# LPC1115_4TE_TOP_V1_1.net
KiCad netlist of a schematic drawn in EAGLE
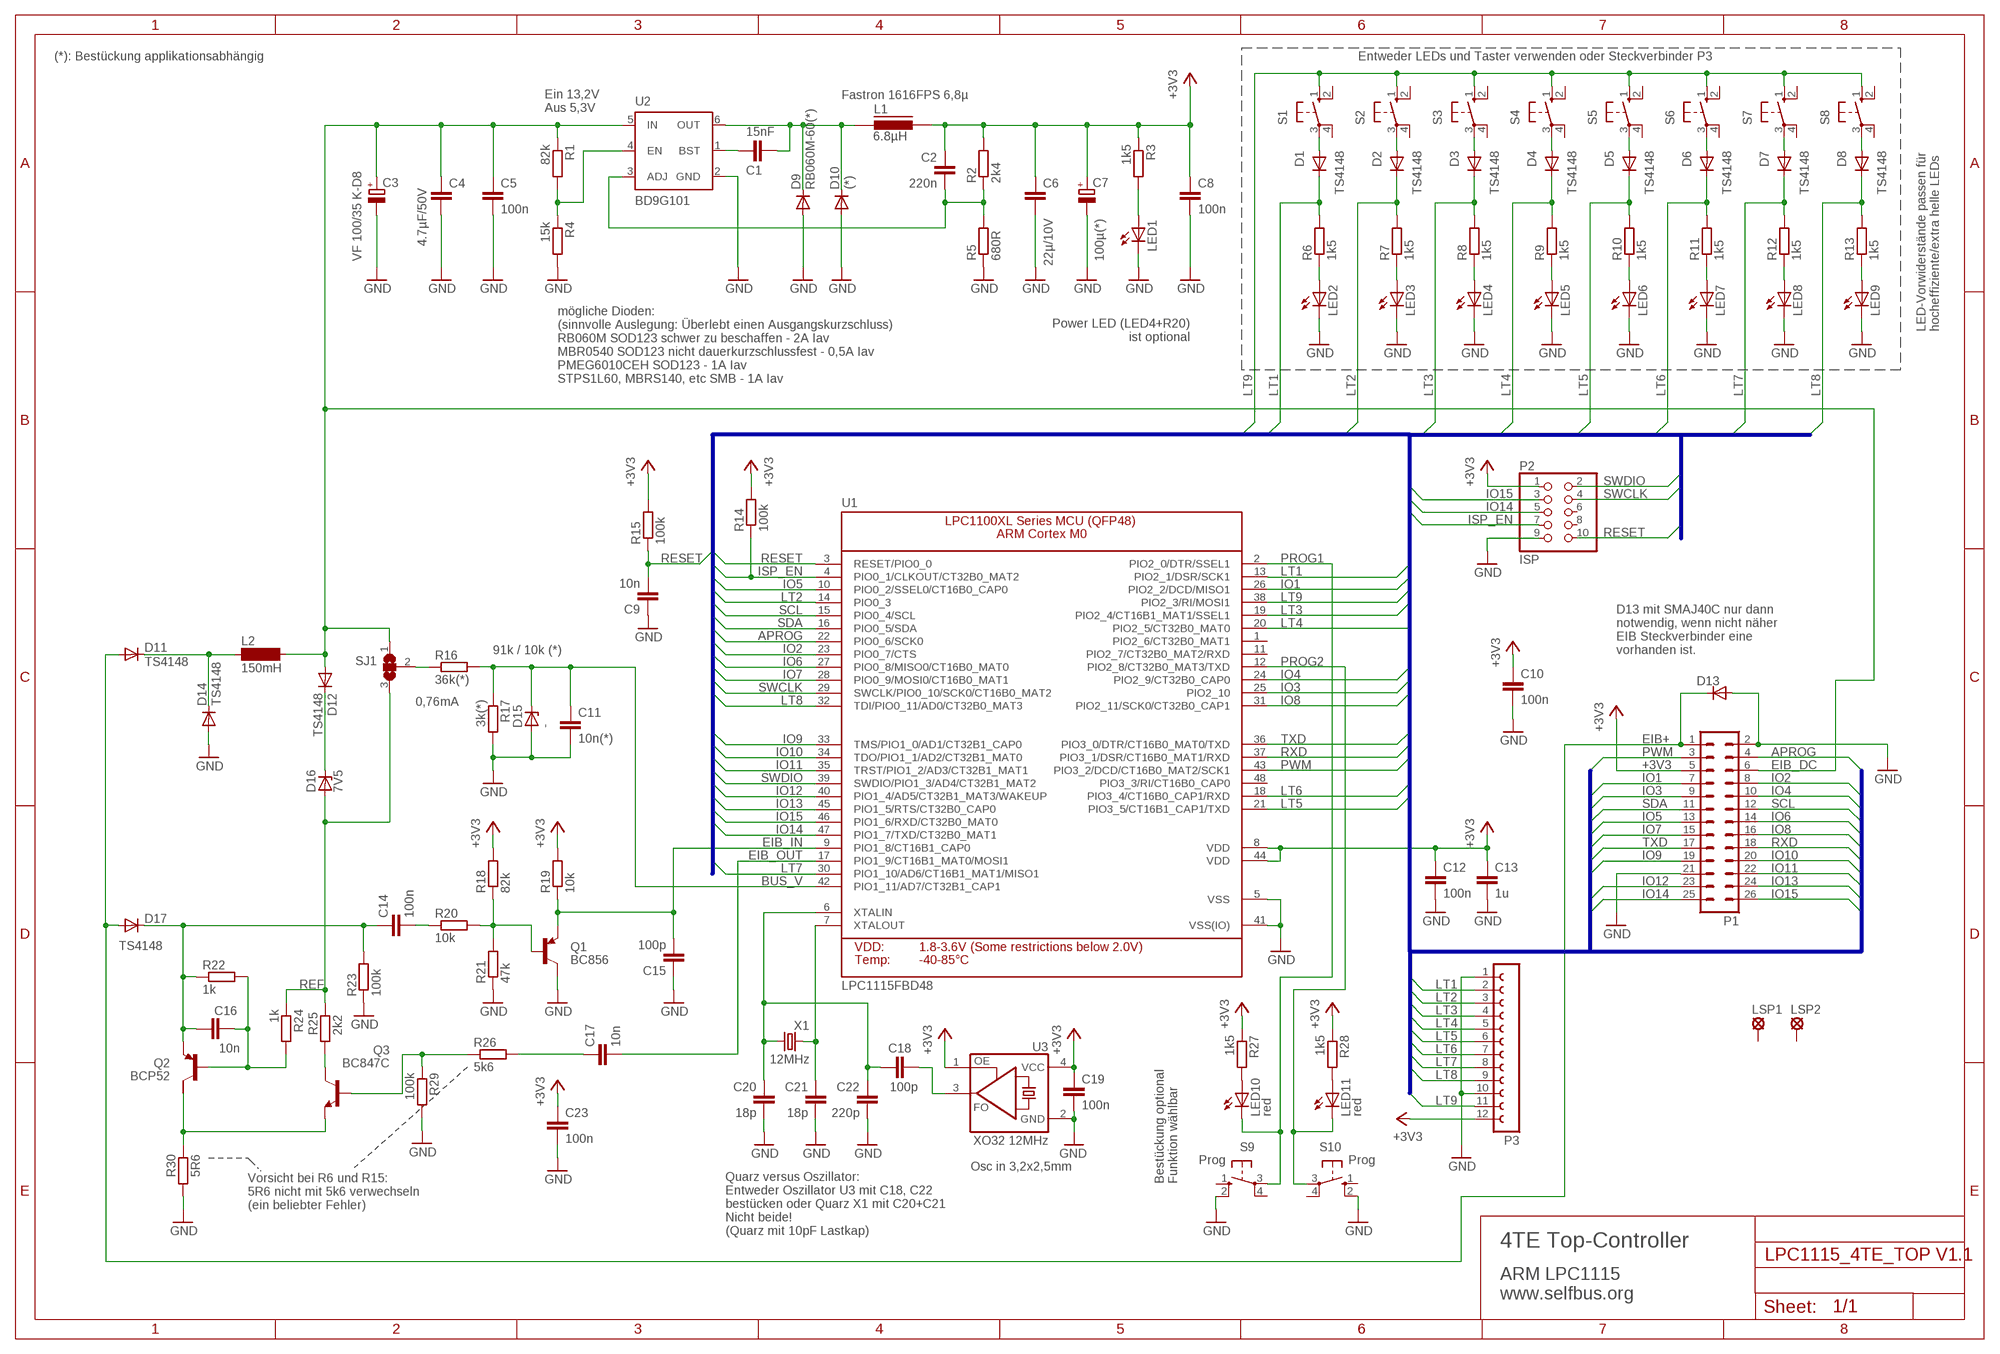
[diagram p0: schematic, sheet 1]

(export (version "E")
  (design (tool "Eeschema 10.0.6"))
  (components
    (comp (ref "C1")
      (value "15nF")
      (footprint "eagle-import:R0805M")
      (libsource (lib "eagle-import") (part "C-EUC0805M"))
    )
    (comp (ref "C2")
      (value "220n")
      (footprint "eagle-import:R0805M")
      (libsource (lib "eagle-import") (part "C-EUC0805M"))
    )
    (comp (ref "C3")
      (value "VF 100/35 K-D8")
      (footprint "eagle-import:ESMD-D")
      (libsource (lib "eagle-import") (part "CPOL-EUESMD-D"))
    )
    (comp (ref "C4")
      (value "4.7µF/50V")
      (footprint "eagle-import:R1206M")
      (libsource (lib "eagle-import") (part "C-EUC1206M"))
    )
    (comp (ref "C5")
      (value "100n")
      (footprint "eagle-import:R0805M")
      (libsource (lib "eagle-import") (part "C-EUC0805M"))
    )
    (comp (ref "C6")
      (value "22µ/10V")
      (footprint "eagle-import:C1210K")
      (libsource (lib "eagle-import") (part "C-EUC1210K"))
    )
    (comp (ref "C7")
      (value "100µ(*)")
      (footprint "eagle-import:ESMD-D")
      (libsource (lib "eagle-import") (part "CPOL-EUESMD-D"))
    )
    (comp (ref "C8")
      (value "100n")
      (footprint "eagle-import:R0805M")
      (libsource (lib "eagle-import") (part "C-EUC0805M"))
    )
    (comp (ref "C9")
      (value "10n")
      (footprint "eagle-import:R0805M")
      (libsource (lib "eagle-import") (part "C-EUC0805M"))
    )
    (comp (ref "C10")
      (value "100n")
      (footprint "eagle-import:R0805M")
      (libsource (lib "eagle-import") (part "C-EUC0805M"))
    )
    (comp (ref "C11")
      (value "10n(*)")
      (footprint "eagle-import:R0805M")
      (libsource (lib "eagle-import") (part "C-EUC0805M"))
    )
    (comp (ref "C12")
      (value "100n")
      (footprint "eagle-import:R0805M")
      (libsource (lib "eagle-import") (part "C-EUC0805M"))
    )
    (comp (ref "C13")
      (value "1u")
      (footprint "eagle-import:R0805M")
      (libsource (lib "eagle-import") (part "C-EUC0805M"))
    )
    (comp (ref "C14")
      (value "100n")
      (footprint "eagle-import:R0805M")
      (libsource (lib "eagle-import") (part "C-EUC0805M"))
    )
    (comp (ref "C15")
      (value "100p")
      (footprint "eagle-import:R0805M")
      (libsource (lib "eagle-import") (part "C-EUC0805M"))
    )
    (comp (ref "C16")
      (value "10n")
      (footprint "eagle-import:R0805M")
      (libsource (lib "eagle-import") (part "C-EUC0805M"))
    )
    (comp (ref "C17")
      (value "10n")
      (footprint "eagle-import:R0805M")
      (libsource (lib "eagle-import") (part "C-EUC0805M"))
    )
    (comp (ref "C18")
      (value "100p")
      (footprint "eagle-import:R0805M")
      (libsource (lib "eagle-import") (part "C-EUC0805M"))
    )
    (comp (ref "C19")
      (value "100n")
      (footprint "eagle-import:R0805M")
      (libsource (lib "eagle-import") (part "C-EUC0805M"))
    )
    (comp (ref "C20")
      (value "18p")
      (footprint "eagle-import:R0805M")
      (libsource (lib "eagle-import") (part "C-EUC0805M"))
    )
    (comp (ref "C21")
      (value "18p")
      (footprint "eagle-import:R0805M")
      (libsource (lib "eagle-import") (part "C-EUC0805M"))
    )
    (comp (ref "C22")
      (value "220p")
      (footprint "eagle-import:R0805M")
      (libsource (lib "eagle-import") (part "C-EUC0805M"))
    )
    (comp (ref "C23")
      (value "100n")
      (footprint "eagle-import:R0805M")
      (libsource (lib "eagle-import") (part "C-EUC0805M"))
    )
    (comp (ref "D1")
      (value "TS4148")
      (footprint "eagle-import:D0805")
      (libsource (lib "eagle-import") (part "DIODE-D0805"))
    )
    (comp (ref "D2")
      (value "TS4148")
      (footprint "eagle-import:D0805")
      (libsource (lib "eagle-import") (part "DIODE-D0805"))
    )
    (comp (ref "D3")
      (value "TS4148")
      (footprint "eagle-import:D0805")
      (libsource (lib "eagle-import") (part "DIODE-D0805"))
    )
    (comp (ref "D4")
      (value "TS4148")
      (footprint "eagle-import:D0805")
      (libsource (lib "eagle-import") (part "DIODE-D0805"))
    )
    (comp (ref "D5")
      (value "TS4148")
      (footprint "eagle-import:D0805")
      (libsource (lib "eagle-import") (part "DIODE-D0805"))
    )
    (comp (ref "D6")
      (value "TS4148")
      (footprint "eagle-import:D0805")
      (libsource (lib "eagle-import") (part "DIODE-D0805"))
    )
    (comp (ref "D7")
      (value "TS4148")
      (footprint "eagle-import:D0805")
      (libsource (lib "eagle-import") (part "DIODE-D0805"))
    )
    (comp (ref "D8")
      (value "TS4148")
      (footprint "eagle-import:D0805")
      (libsource (lib "eagle-import") (part "DIODE-D0805"))
    )
    (comp (ref "D9")
      (value "RB060M-60(*)")
      (footprint "eagle-import:SOD123")
      (libsource (lib "eagle-import") (part "DIODE-SOD123"))
    )
    (comp (ref "D10")
      (value "(*)")
      (footprint "eagle-import:SMB")
      (libsource (lib "eagle-import") (part "DIODE-SMB"))
    )
    (comp (ref "D11")
      (value "TS4148")
      (footprint "eagle-import:D0805")
      (libsource (lib "eagle-import") (part "DIODE-D0805"))
    )
    (comp (ref "D12")
      (value "TS4148")
      (footprint "eagle-import:D0805")
      (libsource (lib "eagle-import") (part "DIODE-D0805"))
    )
    (comp (ref "D13")
      (value "D-SMB")
      (footprint "eagle-import:SMB")
      (libsource (lib "eagle-import") (part "D-SMB"))
    )
    (comp (ref "D14")
      (value "TS4148")
      (footprint "eagle-import:D0805")
      (libsource (lib "eagle-import") (part "DIODE-D0805"))
    )
    (comp (ref "D15")
      (value "-")
      (footprint "eagle-import:SOT23")
      (libsource (lib "eagle-import") (part "ZENER-DIODESOT23"))
    )
    (comp (ref "D16")
      (value "7V5")
      (footprint "eagle-import:SOT23")
      (libsource (lib "eagle-import") (part "ZENER-DIODESOT23"))
    )
    (comp (ref "D17")
      (value "TS4148")
      (footprint "eagle-import:D0805")
      (libsource (lib "eagle-import") (part "DIODE-D0805"))
    )
    (comp (ref "L1")
      (value "6.8µH")
      (footprint "eagle-import:1616FPS")
      (libsource (lib "eagle-import") (part "IND_FASTRON_1616FPSB"))
    )
    (comp (ref "L2")
      (value "150mH")
      (footprint "eagle-import:BS11_LIEGEND")
      (libsource (lib "eagle-import") (part "SD12BS11_LIEGEND"))
    )
    (comp (ref "LED1")
      (value "LEDSMT1206")
      (footprint "eagle-import:1206")
      (libsource (lib "eagle-import") (part "LEDSMT1206"))
    )
    (comp (ref "LED2")
      (value "LEDSMT1206")
      (footprint "eagle-import:1206")
      (libsource (lib "eagle-import") (part "LEDSMT1206"))
    )
    (comp (ref "LED3")
      (value "LEDSMT1206")
      (footprint "eagle-import:1206")
      (libsource (lib "eagle-import") (part "LEDSMT1206"))
    )
    (comp (ref "LED4")
      (value "LEDSMT1206")
      (footprint "eagle-import:1206")
      (libsource (lib "eagle-import") (part "LEDSMT1206"))
    )
    (comp (ref "LED5")
      (value "LEDSMT1206")
      (footprint "eagle-import:1206")
      (libsource (lib "eagle-import") (part "LEDSMT1206"))
    )
    (comp (ref "LED6")
      (value "LEDSMT1206")
      (footprint "eagle-import:1206")
      (libsource (lib "eagle-import") (part "LEDSMT1206"))
    )
    (comp (ref "LED7")
      (value "LEDSMT1206")
      (footprint "eagle-import:1206")
      (libsource (lib "eagle-import") (part "LEDSMT1206"))
    )
    (comp (ref "LED8")
      (value "LEDSMT1206")
      (footprint "eagle-import:1206")
      (libsource (lib "eagle-import") (part "LEDSMT1206"))
    )
    (comp (ref "LED9")
      (value "LEDSMT1206")
      (footprint "eagle-import:1206")
      (libsource (lib "eagle-import") (part "LEDSMT1206"))
    )
    (comp (ref "LED10")
      (value "red")
      (footprint "eagle-import:1206")
      (libsource (lib "eagle-import") (part "LEDSMT1206"))
    )
    (comp (ref "LED11")
      (value "red")
      (footprint "eagle-import:1206")
      (libsource (lib "eagle-import") (part "LEDSMT1206"))
    )
    (comp (ref "LSP1")
      (value "SE13_SM")
      (footprint "eagle-import:SE13_SM")
      (libsource (lib "eagle-import") (part "SE13_SM"))
    )
    (comp (ref "LSP2")
      (value "SE13_SM")
      (footprint "eagle-import:SE13_SM")
      (libsource (lib "eagle-import") (part "SE13_SM"))
    )
    (comp (ref "P1")
      (value "ML26")
      (footprint "eagle-import:ML26")
      (libsource (lib "eagle-import") (part "ML26"))
    )
    (comp (ref "P2")
      (value "ISP")
      (footprint "eagle-import:2X05M")
      (libsource (lib "eagle-import") (part "PINHD-2X05_2.00"))
    )
    (comp (ref "P3")
      (value "FE12-1")
      (footprint "eagle-import:FE12")
      (libsource (lib "eagle-import") (part "FE12-1"))
    )
    (comp (ref "Q1")
      (value "BC856")
      (footprint "eagle-import:SOT23-BEC")
      (libsource (lib "eagle-import") (part "BC856SMDB"))
    )
    (comp (ref "Q2")
      (value "BCP52")
      (footprint "eagle-import:SOT223")
      (libsource (lib "eagle-import") (part "FZT753SMD"))
    )
    (comp (ref "Q3")
      (value "BC847C")
      (footprint "eagle-import:SOT23")
      (libsource (lib "eagle-import") (part "BC847"))
    )
    (comp (ref "R1")
      (value "82k")
      (footprint "eagle-import:R0805M")
      (libsource (lib "eagle-import") (part "R-EU_R0805M"))
    )
    (comp (ref "R2")
      (value "2k4")
      (footprint "eagle-import:R0805M")
      (libsource (lib "eagle-import") (part "R-EU_R0805M"))
    )
    (comp (ref "R3")
      (value "1k5")
      (footprint "eagle-import:R0805M")
      (libsource (lib "eagle-import") (part "R-EU_R0805M"))
    )
    (comp (ref "R4")
      (value "15k")
      (footprint "eagle-import:R0805M")
      (libsource (lib "eagle-import") (part "R-EU_R0805M"))
    )
    (comp (ref "R5")
      (value "680R")
      (footprint "eagle-import:R0805M")
      (libsource (lib "eagle-import") (part "R-EU_R0805M"))
    )
    (comp (ref "R6")
      (value "1k5")
      (footprint "eagle-import:R0805M")
      (libsource (lib "eagle-import") (part "R-EU_R0805M"))
    )
    (comp (ref "R7")
      (value "1k5")
      (footprint "eagle-import:R0805M")
      (libsource (lib "eagle-import") (part "R-EU_R0805M"))
    )
    (comp (ref "R8")
      (value "1k5")
      (footprint "eagle-import:R0805M")
      (libsource (lib "eagle-import") (part "R-EU_R0805M"))
    )
    (comp (ref "R9")
      (value "1k5")
      (footprint "eagle-import:R0805M")
      (libsource (lib "eagle-import") (part "R-EU_R0805M"))
    )
    (comp (ref "R10")
      (value "1k5")
      (footprint "eagle-import:R0805M")
      (libsource (lib "eagle-import") (part "R-EU_R0805M"))
    )
    (comp (ref "R11")
      (value "1k5")
      (footprint "eagle-import:R0805M")
      (libsource (lib "eagle-import") (part "R-EU_R0805M"))
    )
    (comp (ref "R12")
      (value "1k5")
      (footprint "eagle-import:R0805M")
      (libsource (lib "eagle-import") (part "R-EU_R0805M"))
    )
    (comp (ref "R13")
      (value "1k5")
      (footprint "eagle-import:R0805M")
      (libsource (lib "eagle-import") (part "R-EU_R0805M"))
    )
    (comp (ref "R14")
      (value "100k")
      (footprint "eagle-import:R0805M")
      (libsource (lib "eagle-import") (part "R-EU_R0805M"))
    )
    (comp (ref "R15")
      (value "100k")
      (footprint "eagle-import:R0805M")
      (libsource (lib "eagle-import") (part "R-EU_R0805M"))
    )
    (comp (ref "R16")
      (value "36k(*)")
      (footprint "eagle-import:R0805M")
      (libsource (lib "eagle-import") (part "R-EU_R0805M"))
    )
    (comp (ref "R17")
      (value "3k(*)")
      (footprint "eagle-import:R0805M")
      (libsource (lib "eagle-import") (part "R-EU_R0805M"))
    )
    (comp (ref "R18")
      (value "82k")
      (footprint "eagle-import:R0805M")
      (libsource (lib "eagle-import") (part "R-EU_R0805M"))
    )
    (comp (ref "R19")
      (value "10k")
      (footprint "eagle-import:R0805M")
      (libsource (lib "eagle-import") (part "R-EU_R0805M"))
    )
    (comp (ref "R20")
      (value "10k")
      (footprint "eagle-import:R0805M")
      (libsource (lib "eagle-import") (part "R-EU_R0805M"))
    )
    (comp (ref "R21")
      (value "47k")
      (footprint "eagle-import:R0805M")
      (libsource (lib "eagle-import") (part "R-EU_R0805M"))
    )
    (comp (ref "R22")
      (value "1k")
      (footprint "eagle-import:R0805M")
      (libsource (lib "eagle-import") (part "R-EU_R0805M"))
    )
    (comp (ref "R23")
      (value "100k")
      (footprint "eagle-import:R0805M")
      (libsource (lib "eagle-import") (part "R-EU_R0805M"))
    )
    (comp (ref "R24")
      (value "1k")
      (footprint "eagle-import:R0805M")
      (libsource (lib "eagle-import") (part "R-EU_R0805M"))
    )
    (comp (ref "R25")
      (value "2k2")
      (footprint "eagle-import:R0805M")
      (libsource (lib "eagle-import") (part "R-EU_R0805M"))
    )
    (comp (ref "R26")
      (value "5k6")
      (footprint "eagle-import:R0805M")
      (libsource (lib "eagle-import") (part "R-EU_R0805M"))
    )
    (comp (ref "R27")
      (value "1k5")
      (footprint "eagle-import:R0805M")
      (libsource (lib "eagle-import") (part "R-EU_R0805M"))
    )
    (comp (ref "R28")
      (value "1k5")
      (footprint "eagle-import:R0805M")
      (libsource (lib "eagle-import") (part "R-EU_R0805M"))
    )
    (comp (ref "R29")
      (value "100k")
      (footprint "eagle-import:R0805M")
      (libsource (lib "eagle-import") (part "R-EU_R0805M"))
    )
    (comp (ref "R30")
      (value "5R6")
      (footprint "eagle-import:R1206M")
      (libsource (lib "eagle-import") (part "R-EU_R1206M"))
    )
    (comp (ref "S1")
      (value "10-XXSMD")
      (footprint "eagle-import:B3F-10XX_SMD")
      (libsource (lib "eagle-import") (part "10-XXSMD"))
    )
    (comp (ref "S2")
      (value "10-XXSMD")
      (footprint "eagle-import:B3F-10XX_SMD")
      (libsource (lib "eagle-import") (part "10-XXSMD"))
    )
    (comp (ref "S3")
      (value "10-XXSMD")
      (footprint "eagle-import:B3F-10XX_SMD")
      (libsource (lib "eagle-import") (part "10-XXSMD"))
    )
    (comp (ref "S4")
      (value "10-XXSMD")
      (footprint "eagle-import:B3F-10XX_SMD")
      (libsource (lib "eagle-import") (part "10-XXSMD"))
    )
    (comp (ref "S5")
      (value "10-XXSMD")
      (footprint "eagle-import:B3F-10XX_SMD")
      (libsource (lib "eagle-import") (part "10-XXSMD"))
    )
    (comp (ref "S6")
      (value "10-XXSMD")
      (footprint "eagle-import:B3F-10XX_SMD")
      (libsource (lib "eagle-import") (part "10-XXSMD"))
    )
    (comp (ref "S7")
      (value "10-XXSMD")
      (footprint "eagle-import:B3F-10XX_SMD")
      (libsource (lib "eagle-import") (part "10-XXSMD"))
    )
    (comp (ref "S8")
      (value "10-XXSMD")
      (footprint "eagle-import:B3F-10XX_SMD")
      (libsource (lib "eagle-import") (part "10-XXSMD"))
    )
    (comp (ref "S9")
      (value "Prog")
      (footprint "eagle-import:B3F-10XX_SMD")
      (libsource (lib "eagle-import") (part "10-XXSMD"))
    )
    (comp (ref "S10")
      (value "Prog")
      (footprint "eagle-import:B3F-10XX_SMD")
      (libsource (lib "eagle-import") (part "10-XXSMD"))
    )
    (comp (ref "SJ1")
      (value "SJ2W")
      (footprint "eagle-import:SJ_2")
      (libsource (lib "eagle-import") (part "SJ2W"))
    )
    (comp (ref "U1")
      (value "LPC1115FBD48")
      (footprint "eagle-import:LQFP48")
      (libsource (lib "eagle-import") (part "LPC1113/4/5_QFP48_XLSERIES"))
    )
    (comp (ref "U2")
      (value "BD9G101")
      (footprint "eagle-import:SOT23-6MOD")
      (libsource (lib "eagle-import") (part "BD9G101GBD9G101G-SOT23-6MOD"))
    )
    (comp (ref "U3")
      (value "XO32 12MHz")
      (footprint "eagle-import:ASF")
      (libsource (lib "eagle-import") (part "ASFL"))
    )
    (comp (ref "X1")
      (value "12MHz")
      (footprint "eagle-import:ASF")
      (libsource (lib "eagle-import") (part "CRYSTALASF"))
    )
  )
  (nets
    (net (code "1") (name "+3V3") (class "Default")
      (node (ref "C10") (pin "1") (pinfunction "1_1") (pintype "passive"))
      (node (ref "C12") (pin "1") (pinfunction "1_1") (pintype "passive"))
      (node (ref "C13") (pin "1") (pinfunction "1_1") (pintype "passive"))
      (node (ref "C19") (pin "1") (pinfunction "1_1") (pintype "passive"))
      (node (ref "C2") (pin "1") (pinfunction "1_1") (pintype "passive"))
      (node (ref "C23") (pin "1") (pinfunction "1_1") (pintype "passive"))
      (node (ref "C6") (pin "1") (pinfunction "1_1") (pintype "passive"))
      (node (ref "C7") (pin "+") (pinfunction "+_+") (pintype "passive"))
      (node (ref "C8") (pin "1") (pinfunction "1_1") (pintype "passive"))
      (node (ref "L1") (pin "P$2") (pinfunction "2_P$2") (pintype "passive"))
      (node (ref "P1") (pin "5") (pinfunction "5_5") (pintype "passive"))
      (node (ref "P2") (pin "1") (pinfunction "1_1") (pintype "passive"))
      (node (ref "P3") (pin "12") (pinfunction "12_12") (pintype "passive"))
      (node (ref "R14") (pin "2") (pinfunction "2_2") (pintype "passive"))
      (node (ref "R15") (pin "2") (pinfunction "2_2") (pintype "passive"))
      (node (ref "R18") (pin "2") (pinfunction "2_2") (pintype "passive"))
      (node (ref "R19") (pin "2") (pinfunction "2_2") (pintype "passive"))
      (node (ref "R2") (pin "2") (pinfunction "2_2") (pintype "passive"))
      (node (ref "R27") (pin "1") (pinfunction "1_1") (pintype "passive"))
      (node (ref "R28") (pin "1") (pinfunction "1_1") (pintype "passive"))
      (node (ref "R3") (pin "1") (pinfunction "1_1") (pintype "passive"))
      (node (ref "U1") (pin "44") (pinfunction "VDD_44") (pintype "power_in"))
      (node (ref "U1") (pin "8") (pinfunction "VDD_8") (pintype "power_in"))
      (node (ref "U3") (pin "1") (pinfunction "OE_1") (pintype "input"))
      (node (ref "U3") (pin "4") (pinfunction "VCC_4") (pintype "power_in"))
    )
    (net (code "2") (name "/APROG") (class "Default")
      (node (ref "P1") (pin "4") (pinfunction "4_4") (pintype "passive"))
      (node (ref "U1") (pin "22") (pinfunction "PIO0_6/SCK0_22") (pintype "bidirectional"))
    )
    (net (code "3") (name "/BUS_V") (class "Default")
      (node (ref "C11") (pin "1") (pinfunction "1_1") (pintype "passive"))
      (node (ref "D15") (pin "3") (pinfunction "C_3") (pintype "passive"))
      (node (ref "R16") (pin "2") (pinfunction "2_2") (pintype "passive"))
      (node (ref "R17") (pin "1") (pinfunction "1_1") (pintype "passive"))
      (node (ref "U1") (pin "42") (pinfunction "PIO1_11/AD7/CT32B1_CAP1_42") (pintype "bidirectional"))
    )
    (net (code "4") (name "/EIB+") (class "Default")
      (node (ref "D11") (pin "A") (pinfunction "A_A") (pintype "passive"))
      (node (ref "D13") (pin "1") (pinfunction "C_1") (pintype "passive"))
      (node (ref "D17") (pin "A") (pinfunction "A_A") (pintype "passive"))
      (node (ref "P1") (pin "1") (pinfunction "1_1") (pintype "passive"))
    )
    (net (code "5") (name "/EIB_DC") (class "Default")
      (node (ref "C3") (pin "+") (pinfunction "+_+") (pintype "passive"))
      (node (ref "C4") (pin "1") (pinfunction "1_1") (pintype "passive"))
      (node (ref "C5") (pin "1") (pinfunction "1_1") (pintype "passive"))
      (node (ref "D12") (pin "A") (pinfunction "A_A") (pintype "passive"))
      (node (ref "L2") (pin "2") (pinfunction "2_2") (pintype "passive"))
      (node (ref "P1") (pin "6") (pinfunction "6_6") (pintype "passive"))
      (node (ref "R1") (pin "1") (pinfunction "1_1") (pintype "passive"))
      (node (ref "SJ1") (pin "1") (pinfunction "1_1") (pintype "passive"))
      (node (ref "U2") (pin "5") (pinfunction "IN_5") (pintype "input"))
    )
    (net (code "6") (name "/EIB_IN") (class "Default")
      (node (ref "C15") (pin "2") (pinfunction "2_2") (pintype "passive"))
      (node (ref "Q1") (pin "E") (pinfunction "E_E") (pintype "passive"))
      (node (ref "R19") (pin "1") (pinfunction "1_1") (pintype "passive"))
      (node (ref "U1") (pin "9") (pinfunction "PIO1_8/CT16B1_CAP0_9") (pintype "bidirectional"))
    )
    (net (code "7") (name "/EIB_OUT") (class "Default")
      (node (ref "C17") (pin "2") (pinfunction "2_2") (pintype "passive"))
      (node (ref "U1") (pin "17") (pinfunction "PIO1_9/CT16B1_MAT0/MOSI1_17") (pintype "bidirectional"))
    )
    (net (code "8") (name "/IO1") (class "Default")
      (node (ref "P1") (pin "7") (pinfunction "7_7") (pintype "passive"))
      (node (ref "U1") (pin "26") (pinfunction "PIO2_2/DCD/MISO1_26") (pintype "bidirectional"))
    )
    (net (code "9") (name "/IO2") (class "Default")
      (node (ref "P1") (pin "8") (pinfunction "8_8") (pintype "passive"))
      (node (ref "U1") (pin "23") (pinfunction "PIO0_7/CTS_23") (pintype "bidirectional"))
    )
    (net (code "10") (name "/IO3") (class "Default")
      (node (ref "P1") (pin "9") (pinfunction "9_9") (pintype "passive"))
      (node (ref "U1") (pin "25") (pinfunction "PIO2_10_25") (pintype "bidirectional"))
    )
    (net (code "11") (name "/IO4") (class "Default")
      (node (ref "P1") (pin "10") (pinfunction "10_10") (pintype "passive"))
      (node (ref "U1") (pin "24") (pinfunction "PIO2_9/CT32B0_CAP0_24") (pintype "bidirectional"))
    )
    (net (code "12") (name "/IO5") (class "Default")
      (node (ref "P1") (pin "13") (pinfunction "13_13") (pintype "passive"))
      (node (ref "U1") (pin "10") (pinfunction "PIO0_2/SSEL0/CT16B0_CAP0_10") (pintype "bidirectional"))
    )
    (net (code "13") (name "/IO6") (class "Default")
      (node (ref "P1") (pin "14") (pinfunction "14_14") (pintype "passive"))
      (node (ref "U1") (pin "27") (pinfunction "PIO0_8/MISO0/CT16B0_MAT0_27") (pintype "bidirectional"))
    )
    (net (code "14") (name "/IO7") (class "Default")
      (node (ref "P1") (pin "15") (pinfunction "15_15") (pintype "passive"))
      (node (ref "U1") (pin "28") (pinfunction "PIO0_9/MOSI0/CT16B0_MAT1_28") (pintype "bidirectional"))
    )
    (net (code "15") (name "/IO8") (class "Default")
      (node (ref "P1") (pin "16") (pinfunction "16_16") (pintype "passive"))
      (node (ref "U1") (pin "31") (pinfunction "PIO2_11/SCK0/CT32B0_CAP1_31") (pintype "bidirectional"))
    )
    (net (code "16") (name "/IO9") (class "Default")
      (node (ref "P1") (pin "19") (pinfunction "19_19") (pintype "passive"))
      (node (ref "U1") (pin "33") (pinfunction "TMS/PIO1_0/AD1/CT32B1_CAP0_33") (pintype "bidirectional"))
    )
    (net (code "17") (name "/IO10") (class "Default")
      (node (ref "P1") (pin "20") (pinfunction "20_20") (pintype "passive"))
      (node (ref "U1") (pin "34") (pinfunction "TDO/PIO1_1/AD2/CT32B1_MAT0_34") (pintype "bidirectional"))
    )
    (net (code "18") (name "/IO11") (class "Default")
      (node (ref "P1") (pin "22") (pinfunction "22_22") (pintype "passive"))
      (node (ref "U1") (pin "35") (pinfunction "TRST/PIO1_2/AD3/CT32B1_MAT1_35") (pintype "bidirectional"))
    )
    (net (code "19") (name "/IO12") (class "Default")
      (node (ref "P1") (pin "23") (pinfunction "23_23") (pintype "passive"))
      (node (ref "U1") (pin "40") (pinfunction "PIO1_4/AD5/CT32B1_MAT3/WAKEUP_40") (pintype "bidirectional"))
    )
    (net (code "20") (name "/IO13") (class "Default")
      (node (ref "P1") (pin "24") (pinfunction "24_24") (pintype "passive"))
      (node (ref "U1") (pin "45") (pinfunction "PIO1_5/RTS/CT32B0_CAP0_45") (pintype "bidirectional"))
    )
    (net (code "21") (name "/IO14") (class "Default")
      (node (ref "P1") (pin "25") (pinfunction "25_25") (pintype "passive"))
      (node (ref "P2") (pin "5") (pinfunction "5_5") (pintype "passive"))
      (node (ref "U1") (pin "47") (pinfunction "PIO1_7/TXD/CT32B0_MAT1_47") (pintype "bidirectional"))
    )
    (net (code "22") (name "/IO15") (class "Default")
      (node (ref "P1") (pin "26") (pinfunction "26_26") (pintype "passive"))
      (node (ref "P2") (pin "3") (pinfunction "3_3") (pintype "passive"))
      (node (ref "U1") (pin "46") (pinfunction "PIO1_6/RXD/CT32B0_MAT0_46") (pintype "bidirectional"))
    )
    (net (code "23") (name "/ISP_EN") (class "Default")
      (node (ref "P2") (pin "7") (pinfunction "7_7") (pintype "passive"))
      (node (ref "R14") (pin "1") (pinfunction "1_1") (pintype "passive"))
      (node (ref "U1") (pin "4") (pinfunction "PIO0_1/CLKOUT/CT32B0_MAT2_4") (pintype "bidirectional"))
    )
    (net (code "24") (name "/LT1") (class "Default")
      (node (ref "D1") (pin "C") (pinfunction "C_C") (pintype "passive"))
      (node (ref "P3") (pin "2") (pinfunction "2_2") (pintype "passive"))
      (node (ref "R6") (pin "2") (pinfunction "2_2") (pintype "passive"))
      (node (ref "U1") (pin "13") (pinfunction "PIO2_1/DSR/SCK1_13") (pintype "bidirectional"))
    )
    (net (code "25") (name "/LT2") (class "Default")
      (node (ref "D2") (pin "C") (pinfunction "C_C") (pintype "passive"))
      (node (ref "P3") (pin "3") (pinfunction "3_3") (pintype "passive"))
      (node (ref "R7") (pin "2") (pinfunction "2_2") (pintype "passive"))
      (node (ref "U1") (pin "14") (pinfunction "PIO0_3_14") (pintype "bidirectional"))
    )
    (net (code "26") (name "/LT3") (class "Default")
      (node (ref "D3") (pin "C") (pinfunction "C_C") (pintype "passive"))
      (node (ref "P3") (pin "4") (pinfunction "4_4") (pintype "passive"))
      (node (ref "R8") (pin "2") (pinfunction "2_2") (pintype "passive"))
      (node (ref "U1") (pin "19") (pinfunction "PIO2_4/CT16B1_MAT1/SSEL1_19") (pintype "bidirectional"))
    )
    (net (code "27") (name "/LT4") (class "Default")
      (node (ref "D4") (pin "C") (pinfunction "C_C") (pintype "passive"))
      (node (ref "P3") (pin "5") (pinfunction "5_5") (pintype "passive"))
      (node (ref "R9") (pin "2") (pinfunction "2_2") (pintype "passive"))
      (node (ref "U1") (pin "20") (pinfunction "PIO2_5/CT32B0_MAT0_20") (pintype "bidirectional"))
    )
    (net (code "28") (name "/LT5") (class "Default")
      (node (ref "D5") (pin "C") (pinfunction "C_C") (pintype "passive"))
      (node (ref "P3") (pin "6") (pinfunction "6_6") (pintype "passive"))
      (node (ref "R10") (pin "2") (pinfunction "2_2") (pintype "passive"))
      (node (ref "U1") (pin "21") (pinfunction "PIO3_5/CT16B1_CAP1/TXD_21") (pintype "bidirectional"))
    )
    (net (code "29") (name "/LT6") (class "Default")
      (node (ref "D6") (pin "C") (pinfunction "C_C") (pintype "passive"))
      (node (ref "P3") (pin "7") (pinfunction "7_7") (pintype "passive"))
      (node (ref "R11") (pin "2") (pinfunction "2_2") (pintype "passive"))
      (node (ref "U1") (pin "18") (pinfunction "PIO3_4/CT16B0_CAP1/RXD_18") (pintype "bidirectional"))
    )
    (net (code "30") (name "/LT7") (class "Default")
      (node (ref "D7") (pin "C") (pinfunction "C_C") (pintype "passive"))
      (node (ref "P3") (pin "8") (pinfunction "8_8") (pintype "passive"))
      (node (ref "R12") (pin "2") (pinfunction "2_2") (pintype "passive"))
      (node (ref "U1") (pin "30") (pinfunction "PIO1_10/AD6/CT16B1_MAT1/MISO1_30") (pintype "bidirectional"))
    )
    (net (code "31") (name "/LT8") (class "Default")
      (node (ref "D8") (pin "C") (pinfunction "C_C") (pintype "passive"))
      (node (ref "P3") (pin "9") (pinfunction "9_9") (pintype "passive"))
      (node (ref "R13") (pin "2") (pinfunction "2_2") (pintype "passive"))
      (node (ref "U1") (pin "32") (pinfunction "TDI/PIO0_11/AD0/CT32B0_MAT3_32") (pintype "bidirectional"))
    )
    (net (code "32") (name "/LT9") (class "Default")
      (node (ref "P3") (pin "11") (pinfunction "11_11") (pintype "passive"))
      (node (ref "S1") (pin "1") (pinfunction "S_1") (pintype "passive"))
      (node (ref "S2") (pin "1") (pinfunction "S_1") (pintype "passive"))
      (node (ref "S3") (pin "1") (pinfunction "S_1") (pintype "passive"))
      (node (ref "S4") (pin "1") (pinfunction "S_1") (pintype "passive"))
      (node (ref "S5") (pin "1") (pinfunction "S_1") (pintype "passive"))
      (node (ref "S6") (pin "1") (pinfunction "S_1") (pintype "passive"))
      (node (ref "S7") (pin "1") (pinfunction "S_1") (pintype "passive"))
      (node (ref "S8") (pin "1") (pinfunction "S_1") (pintype "passive"))
      (node (ref "U1") (pin "38") (pinfunction "PIO2_3/RI/MOSI1_38") (pintype "bidirectional"))
    )
    (net (code "33") (name "/PROG1") (class "Default")
      (node (ref "LED10") (pin "C") (pinfunction "C_C") (pintype "passive"))
      (node (ref "S9") (pin "3") (pinfunction "P_3") (pintype "passive"))
      (node (ref "U1") (pin "2") (pinfunction "PIO2_0/DTR/SSEL1_2") (pintype "bidirectional"))
    )
    (net (code "34") (name "/PROG2") (class "Default")
      (node (ref "LED11") (pin "C") (pinfunction "C_C") (pintype "passive"))
      (node (ref "S10") (pin "3") (pinfunction "P_3") (pintype "passive"))
      (node (ref "U1") (pin "12") (pinfunction "PIO2_8/CT32B0_MAT3/TXD_12") (pintype "bidirectional"))
    )
    (net (code "35") (name "/PWM") (class "Default")
      (node (ref "P1") (pin "3") (pinfunction "3_3") (pintype "passive"))
      (node (ref "U1") (pin "43") (pinfunction "PIO3_2/DCD/CT16B0_MAT2/SCK1_43") (pintype "bidirectional"))
    )
    (net (code "36") (name "/REF") (class "Default")
      (node (ref "D16") (pin "1") (pinfunction "A_1") (pintype "passive"))
      (node (ref "R24") (pin "1") (pinfunction "1_1") (pintype "passive"))
      (node (ref "R25") (pin "2") (pinfunction "2_2") (pintype "passive"))
      (node (ref "SJ1") (pin "3") (pinfunction "3_3") (pintype "passive"))
    )
    (net (code "37") (name "/RESET") (class "Default")
      (node (ref "C9") (pin "2") (pinfunction "2_2") (pintype "passive"))
      (node (ref "P2") (pin "10") (pinfunction "10_10") (pintype "passive"))
      (node (ref "R15") (pin "1") (pinfunction "1_1") (pintype "passive"))
      (node (ref "U1") (pin "3") (pinfunction "RESET/PIO0_0_3") (pintype "bidirectional"))
    )
    (net (code "38") (name "/RXD") (class "Default")
      (node (ref "P1") (pin "18") (pinfunction "18_18") (pintype "passive"))
      (node (ref "U1") (pin "37") (pinfunction "PIO3_1/DSR/CT16B0_MAT1/RXD_37") (pintype "bidirectional"))
    )
    (net (code "39") (name "/SCL") (class "Default")
      (node (ref "P1") (pin "12") (pinfunction "12_12") (pintype "passive"))
      (node (ref "U1") (pin "15") (pinfunction "PIO0_4/SCL_15") (pintype "bidirectional"))
    )
    (net (code "40") (name "/SDA") (class "Default")
      (node (ref "P1") (pin "11") (pinfunction "11_11") (pintype "passive"))
      (node (ref "U1") (pin "16") (pinfunction "PIO0_5/SDA_16") (pintype "bidirectional"))
    )
    (net (code "41") (name "/SWCLK") (class "Default")
      (node (ref "P2") (pin "4") (pinfunction "4_4") (pintype "passive"))
      (node (ref "U1") (pin "29") (pinfunction "SWCLK/PIO0_10/SCK0/CT16B0_MAT2_29") (pintype "bidirectional"))
    )
    (net (code "42") (name "/SWDIO") (class "Default")
      (node (ref "P2") (pin "2") (pinfunction "2_2") (pintype "passive"))
      (node (ref "U1") (pin "39") (pinfunction "SWDIO/PIO1_3/AD4/CT32B1_MAT2_39") (pintype "bidirectional"))
    )
    (net (code "43") (name "/TXD") (class "Default")
      (node (ref "P1") (pin "17") (pinfunction "17_17") (pintype "passive"))
      (node (ref "U1") (pin "36") (pinfunction "PIO3_0/DTR/CT16B0_MAT0/TXD_36") (pintype "bidirectional"))
    )
    (net (code "44") (name "GND") (class "Default")
      (node (ref "C10") (pin "2") (pinfunction "2_2") (pintype "passive"))
      (node (ref "C11") (pin "2") (pinfunction "2_2") (pintype "passive"))
      (node (ref "C12") (pin "2") (pinfunction "2_2") (pintype "passive"))
      (node (ref "C13") (pin "2") (pinfunction "2_2") (pintype "passive"))
      (node (ref "C15") (pin "1") (pinfunction "1_1") (pintype "passive"))
      (node (ref "C19") (pin "2") (pinfunction "2_2") (pintype "passive"))
      (node (ref "C20") (pin "2") (pinfunction "2_2") (pintype "passive"))
      (node (ref "C21") (pin "2") (pinfunction "2_2") (pintype "passive"))
      (node (ref "C22") (pin "2") (pinfunction "2_2") (pintype "passive"))
      (node (ref "C23") (pin "2") (pinfunction "2_2") (pintype "passive"))
      (node (ref "C3") (pin "-") (pinfunction "-_-") (pintype "passive"))
      (node (ref "C4") (pin "2") (pinfunction "2_2") (pintype "passive"))
      (node (ref "C5") (pin "2") (pinfunction "2_2") (pintype "passive"))
      (node (ref "C6") (pin "2") (pinfunction "2_2") (pintype "passive"))
      (node (ref "C7") (pin "-") (pinfunction "-_-") (pintype "passive"))
      (node (ref "C8") (pin "2") (pinfunction "2_2") (pintype "passive"))
      (node (ref "C9") (pin "1") (pinfunction "1_1") (pintype "passive"))
      (node (ref "D10") (pin "A") (pinfunction "A_A") (pintype "passive"))
      (node (ref "D13") (pin "2") (pinfunction "A_2") (pintype "passive"))
      (node (ref "D14") (pin "A") (pinfunction "A_A") (pintype "passive"))
      (node (ref "D15") (pin "1") (pinfunction "A_1") (pintype "passive"))
      (node (ref "D9") (pin "A") (pinfunction "A_A") (pintype "passive"))
      (node (ref "LED1") (pin "C") (pinfunction "C_C") (pintype "passive"))
      (node (ref "LED2") (pin "C") (pinfunction "C_C") (pintype "passive"))
      (node (ref "LED3") (pin "C") (pinfunction "C_C") (pintype "passive"))
      (node (ref "LED4") (pin "C") (pinfunction "C_C") (pintype "passive"))
      (node (ref "LED5") (pin "C") (pinfunction "C_C") (pintype "passive"))
      (node (ref "LED6") (pin "C") (pinfunction "C_C") (pintype "passive"))
      (node (ref "LED7") (pin "C") (pinfunction "C_C") (pintype "passive"))
      (node (ref "LED8") (pin "C") (pinfunction "C_C") (pintype "passive"))
      (node (ref "LED9") (pin "C") (pinfunction "C_C") (pintype "passive"))
      (node (ref "P1") (pin "2") (pinfunction "2_2") (pintype "passive"))
      (node (ref "P1") (pin "21") (pinfunction "21_21") (pintype "passive"))
      (node (ref "P2") (pin "9") (pinfunction "9_9") (pintype "passive"))
      (node (ref "P3") (pin "1") (pinfunction "1_1") (pintype "passive"))
      (node (ref "P3") (pin "10") (pinfunction "10_10") (pintype "passive"))
      (node (ref "Q1") (pin "C") (pinfunction "C_C") (pintype "passive"))
      (node (ref "R17") (pin "2") (pinfunction "2_2") (pintype "passive"))
      (node (ref "R21") (pin "1") (pinfunction "1_1") (pintype "passive"))
      (node (ref "R23") (pin "1") (pinfunction "1_1") (pintype "passive"))
      (node (ref "R29") (pin "2") (pinfunction "2_2") (pintype "passive"))
      (node (ref "R30") (pin "1") (pinfunction "1_1") (pintype "passive"))
      (node (ref "R4") (pin "2") (pinfunction "2_2") (pintype "passive"))
      (node (ref "R5") (pin "1") (pinfunction "1_1") (pintype "passive"))
      (node (ref "S10") (pin "2") (pinfunction "S1_2") (pintype "passive"))
      (node (ref "S9") (pin "2") (pinfunction "S1_2") (pintype "passive"))
      (node (ref "U1") (pin "41") (pinfunction "VSS(IO)_41") (pintype "power_in"))
      (node (ref "U1") (pin "5") (pinfunction "VSS_5") (pintype "power_in"))
      (node (ref "U2") (pin "2") (pinfunction "GND_2") (pintype "power_in"))
      (node (ref "U3") (pin "2") (pinfunction "GND_2") (pintype "power_in"))
    )
    (net (code "45") (name "Net-(C14-Pad2)") (class "Default")
      (node (ref "C14") (pin "2") (pinfunction "2_2") (pintype "passive"))
      (node (ref "R20") (pin "1") (pinfunction "1_1") (pintype "passive"))
    )
    (net (code "46") (name "Net-(C17-Pad1)") (class "Default")
      (node (ref "C17") (pin "1") (pinfunction "1_1") (pintype "passive"))
      (node (ref "R26") (pin "2") (pinfunction "2_2") (pintype "passive"))
    )
    (net (code "47") (name "Net-(D11-PadC)") (class "Default")
      (node (ref "D11") (pin "C") (pinfunction "C_C") (pintype "passive"))
      (node (ref "D14") (pin "C") (pinfunction "C_C") (pintype "passive"))
      (node (ref "L2") (pin "1") (pinfunction "1_1") (pintype "passive"))
    )
    (net (code "48") (name "Net-(D16-C)") (class "Default")
      (node (ref "D12") (pin "C") (pinfunction "C_C") (pintype "passive"))
      (node (ref "D16") (pin "3") (pinfunction "C_3") (pintype "passive"))
    )
    (net (code "49") (name "Net-(L1-1)") (class "Default")
      (node (ref "C1") (pin "1") (pinfunction "1_1") (pintype "passive"))
      (node (ref "D10") (pin "C") (pinfunction "C_C") (pintype "passive"))
      (node (ref "D9") (pin "C") (pinfunction "C_C") (pintype "passive"))
      (node (ref "L1") (pin "P$1") (pinfunction "1_P$1") (pintype "passive"))
      (node (ref "U2") (pin "6") (pinfunction "OUT_6") (pintype "output"))
    )
    (net (code "50") (name "Net-(LED1-PadA)") (class "Default")
      (node (ref "LED1") (pin "A") (pinfunction "A_A") (pintype "passive"))
      (node (ref "R3") (pin "2") (pinfunction "2_2") (pintype "passive"))
    )
    (net (code "51") (name "Net-(LED2-PadA)") (class "Default")
      (node (ref "LED2") (pin "A") (pinfunction "A_A") (pintype "passive"))
      (node (ref "R6") (pin "1") (pinfunction "1_1") (pintype "passive"))
    )
    (net (code "52") (name "Net-(LED3-PadA)") (class "Default")
      (node (ref "LED3") (pin "A") (pinfunction "A_A") (pintype "passive"))
      (node (ref "R7") (pin "1") (pinfunction "1_1") (pintype "passive"))
    )
    (net (code "53") (name "Net-(LED4-PadA)") (class "Default")
      (node (ref "LED4") (pin "A") (pinfunction "A_A") (pintype "passive"))
      (node (ref "R8") (pin "1") (pinfunction "1_1") (pintype "passive"))
    )
    (net (code "54") (name "Net-(LED5-PadA)") (class "Default")
      (node (ref "LED5") (pin "A") (pinfunction "A_A") (pintype "passive"))
      (node (ref "R9") (pin "1") (pinfunction "1_1") (pintype "passive"))
    )
    (net (code "55") (name "Net-(LED6-PadA)") (class "Default")
      (node (ref "LED6") (pin "A") (pinfunction "A_A") (pintype "passive"))
      (node (ref "R10") (pin "1") (pinfunction "1_1") (pintype "passive"))
    )
    (net (code "56") (name "Net-(LED7-PadA)") (class "Default")
      (node (ref "LED7") (pin "A") (pinfunction "A_A") (pintype "passive"))
      (node (ref "R11") (pin "1") (pinfunction "1_1") (pintype "passive"))
    )
    (net (code "57") (name "Net-(LED8-PadA)") (class "Default")
      (node (ref "LED8") (pin "A") (pinfunction "A_A") (pintype "passive"))
      (node (ref "R12") (pin "1") (pinfunction "1_1") (pintype "passive"))
    )
    (net (code "58") (name "Net-(LED9-PadA)") (class "Default")
      (node (ref "LED9") (pin "A") (pinfunction "A_A") (pintype "passive"))
      (node (ref "R13") (pin "1") (pinfunction "1_1") (pintype "passive"))
    )
    (net (code "59") (name "Net-(LED10-PadA)") (class "Default")
      (node (ref "LED10") (pin "A") (pinfunction "A_A") (pintype "passive"))
      (node (ref "R27") (pin "2") (pinfunction "2_2") (pintype "passive"))
    )
    (net (code "60") (name "Net-(LED11-PadA)") (class "Default")
      (node (ref "LED11") (pin "A") (pinfunction "A_A") (pintype "passive"))
      (node (ref "R28") (pin "2") (pinfunction "2_2") (pintype "passive"))
    )
    (net (code "61") (name "Net-(Q1-PadB)") (class "Default")
      (node (ref "Q1") (pin "B") (pinfunction "B_B") (pintype "passive"))
      (node (ref "R18") (pin "1") (pinfunction "1_1") (pintype "passive"))
      (node (ref "R20") (pin "2") (pinfunction "2_2") (pintype "passive"))
      (node (ref "R21") (pin "2") (pinfunction "2_2") (pintype "passive"))
    )
    (net (code "62") (name "Net-(Q2-B)") (class "Default")
      (node (ref "C16") (pin "2") (pinfunction "2_2") (pintype "passive"))
      (node (ref "Q2") (pin "1") (pinfunction "B_1") (pintype "passive"))
      (node (ref "R22") (pin "2") (pinfunction "2_2") (pintype "passive"))
      (node (ref "R24") (pin "2") (pinfunction "2_2") (pintype "passive"))
    )
    (net (code "63") (name "Net-(Q2-C)") (class "Default")
      (node (ref "Q2") (pin "2") (pinfunction "C_2") (pintype "passive"))
      (node (ref "Q3") (pin "2") (pinfunction "E_2") (pintype "passive"))
      (node (ref "R30") (pin "2") (pinfunction "2_2") (pintype "passive"))
    )
    (net (code "64") (name "Net-(Q2-E)") (class "Default")
      (node (ref "C14") (pin "1") (pinfunction "1_1") (pintype "passive"))
      (node (ref "C16") (pin "1") (pinfunction "1_1") (pintype "passive"))
      (node (ref "D17") (pin "C") (pinfunction "C_C") (pintype "passive"))
      (node (ref "Q2") (pin "3") (pinfunction "E_3") (pintype "passive"))
      (node (ref "R22") (pin "1") (pinfunction "1_1") (pintype "passive"))
      (node (ref "R23") (pin "2") (pinfunction "2_2") (pintype "passive"))
    )
    (net (code "65") (name "Net-(Q3-B)") (class "Default")
      (node (ref "Q3") (pin "1") (pinfunction "B_1") (pintype "passive"))
      (node (ref "R26") (pin "1") (pinfunction "1_1") (pintype "passive"))
      (node (ref "R29") (pin "1") (pinfunction "1_1") (pintype "passive"))
    )
    (net (code "66") (name "Net-(Q3-C)") (class "Default")
      (node (ref "Q3") (pin "3") (pinfunction "C_3") (pintype "passive"))
      (node (ref "R25") (pin "1") (pinfunction "1_1") (pintype "passive"))
    )
    (net (code "67") (name "Net-(R16-Pad1)") (class "Default")
      (node (ref "R16") (pin "1") (pinfunction "1_1") (pintype "passive"))
      (node (ref "SJ1") (pin "2") (pinfunction "2_2") (pintype "passive"))
    )
    (net (code "68") (name "Net-(S1-P)") (class "Default")
      (node (ref "D1") (pin "A") (pinfunction "A_A") (pintype "passive"))
      (node (ref "S1") (pin "3") (pinfunction "P_3") (pintype "passive"))
    )
    (net (code "69") (name "Net-(S2-P)") (class "Default")
      (node (ref "D2") (pin "A") (pinfunction "A_A") (pintype "passive"))
      (node (ref "S2") (pin "3") (pinfunction "P_3") (pintype "passive"))
    )
    (net (code "70") (name "Net-(S3-P)") (class "Default")
      (node (ref "D3") (pin "A") (pinfunction "A_A") (pintype "passive"))
      (node (ref "S3") (pin "3") (pinfunction "P_3") (pintype "passive"))
    )
    (net (code "71") (name "Net-(S4-P)") (class "Default")
      (node (ref "D4") (pin "A") (pinfunction "A_A") (pintype "passive"))
      (node (ref "S4") (pin "3") (pinfunction "P_3") (pintype "passive"))
    )
    (net (code "72") (name "Net-(S5-P)") (class "Default")
      (node (ref "D5") (pin "A") (pinfunction "A_A") (pintype "passive"))
      (node (ref "S5") (pin "3") (pinfunction "P_3") (pintype "passive"))
    )
    (net (code "73") (name "Net-(S6-P)") (class "Default")
      (node (ref "D6") (pin "A") (pinfunction "A_A") (pintype "passive"))
      (node (ref "S6") (pin "3") (pinfunction "P_3") (pintype "passive"))
    )
    (net (code "74") (name "Net-(S7-P)") (class "Default")
      (node (ref "D7") (pin "A") (pinfunction "A_A") (pintype "passive"))
      (node (ref "S7") (pin "3") (pinfunction "P_3") (pintype "passive"))
    )
    (net (code "75") (name "Net-(S8-P)") (class "Default")
      (node (ref "D8") (pin "A") (pinfunction "A_A") (pintype "passive"))
      (node (ref "S8") (pin "3") (pinfunction "P_3") (pintype "passive"))
    )
    (net (code "76") (name "Net-(U1-XTALIN)") (class "Default")
      (node (ref "C18") (pin "2") (pinfunction "2_2") (pintype "passive"))
      (node (ref "C20") (pin "1") (pinfunction "1_1") (pintype "passive"))
      (node (ref "C22") (pin "1") (pinfunction "1_1") (pintype "passive"))
      (node (ref "U1") (pin "6") (pinfunction "XTALIN_6") (pintype "input"))
      (node (ref "X1") (pin "3") (pinfunction "2_3") (pintype "passive"))
    )
    (net (code "77") (name "Net-(U1-XTALOUT)") (class "Default")
      (node (ref "C21") (pin "1") (pinfunction "1_1") (pintype "passive"))
      (node (ref "U1") (pin "7") (pinfunction "XTALOUT_7") (pintype "output"))
      (node (ref "X1") (pin "1") (pinfunction "1_1") (pintype "passive"))
    )
    (net (code "78") (name "Net-(U2-ADJ)") (class "Default")
      (node (ref "C2") (pin "2") (pinfunction "2_2") (pintype "passive"))
      (node (ref "R2") (pin "1") (pinfunction "1_1") (pintype "passive"))
      (node (ref "R5") (pin "2") (pinfunction "2_2") (pintype "passive"))
      (node (ref "U2") (pin "3") (pinfunction "ADJ_3") (pintype "passive"))
    )
    (net (code "79") (name "Net-(U2-BST)") (class "Default")
      (node (ref "C1") (pin "2") (pinfunction "2_2") (pintype "passive"))
      (node (ref "U2") (pin "1") (pinfunction "BST_1") (pintype "output"))
    )
    (net (code "80") (name "Net-(U2-EN)") (class "Default")
      (node (ref "R1") (pin "2") (pinfunction "2_2") (pintype "passive"))
      (node (ref "R4") (pin "1") (pinfunction "1_1") (pintype "passive"))
      (node (ref "U2") (pin "4") (pinfunction "EN_4") (pintype "input"))
    )
    (net (code "81") (name "Net-(U3-FO)") (class "Default")
      (node (ref "C18") (pin "1") (pinfunction "1_1") (pintype "passive"))
      (node (ref "U3") (pin "3") (pinfunction "FO_3") (pintype "output"))
    )
    (net (code "82") (name "unconnected-(LSP1-PadMP)") (class "Default")
      (node (ref "LSP1") (pin "MP") (pinfunction "MP_MP") (pintype "passive"))
    )
    (net (code "83") (name "unconnected-(LSP2-PadMP)") (class "Default")
      (node (ref "LSP2") (pin "MP") (pinfunction "MP_MP") (pintype "passive"))
    )
    (net (code "84") (name "unconnected-(P2-Pad6)") (class "Default")
      (node (ref "P2") (pin "6") (pinfunction "6_6") (pintype "passive"))
    )
    (net (code "85") (name "unconnected-(P2-Pad8)") (class "Default")
      (node (ref "P2") (pin "8") (pinfunction "8_8") (pintype "passive"))
    )
    (net (code "86") (name "unconnected-(Q2-C{slash}-Pad4)") (class "Default")
      (node (ref "Q2") (pin "4") (pinfunction "C/_4") (pintype "passive"))
    )
    (net (code "87") (name "unconnected-(S1-P1-Pad4)") (class "Default")
      (node (ref "S1") (pin "4") (pinfunction "P1_4") (pintype "passive"))
    )
    (net (code "88") (name "unconnected-(S1-S1-Pad2)") (class "Default")
      (node (ref "S1") (pin "2") (pinfunction "S1_2") (pintype "passive"))
    )
    (net (code "89") (name "unconnected-(S2-P1-Pad4)") (class "Default")
      (node (ref "S2") (pin "4") (pinfunction "P1_4") (pintype "passive"))
    )
    (net (code "90") (name "unconnected-(S2-S1-Pad2)") (class "Default")
      (node (ref "S2") (pin "2") (pinfunction "S1_2") (pintype "passive"))
    )
    (net (code "91") (name "unconnected-(S3-P1-Pad4)") (class "Default")
      (node (ref "S3") (pin "4") (pinfunction "P1_4") (pintype "passive"))
    )
    (net (code "92") (name "unconnected-(S3-S1-Pad2)") (class "Default")
      (node (ref "S3") (pin "2") (pinfunction "S1_2") (pintype "passive"))
    )
    (net (code "93") (name "unconnected-(S4-P1-Pad4)") (class "Default")
      (node (ref "S4") (pin "4") (pinfunction "P1_4") (pintype "passive"))
    )
    (net (code "94") (name "unconnected-(S4-S1-Pad2)") (class "Default")
      (node (ref "S4") (pin "2") (pinfunction "S1_2") (pintype "passive"))
    )
    (net (code "95") (name "unconnected-(S5-P1-Pad4)") (class "Default")
      (node (ref "S5") (pin "4") (pinfunction "P1_4") (pintype "passive"))
    )
    (net (code "96") (name "unconnected-(S5-S1-Pad2)") (class "Default")
      (node (ref "S5") (pin "2") (pinfunction "S1_2") (pintype "passive"))
    )
    (net (code "97") (name "unconnected-(S6-P1-Pad4)") (class "Default")
      (node (ref "S6") (pin "4") (pinfunction "P1_4") (pintype "passive"))
    )
    (net (code "98") (name "unconnected-(S6-S1-Pad2)") (class "Default")
      (node (ref "S6") (pin "2") (pinfunction "S1_2") (pintype "passive"))
    )
    (net (code "99") (name "unconnected-(S7-P1-Pad4)") (class "Default")
      (node (ref "S7") (pin "4") (pinfunction "P1_4") (pintype "passive"))
    )
    (net (code "100") (name "unconnected-(S7-S1-Pad2)") (class "Default")
      (node (ref "S7") (pin "2") (pinfunction "S1_2") (pintype "passive"))
    )
    (net (code "101") (name "unconnected-(S8-P1-Pad4)") (class "Default")
      (node (ref "S8") (pin "4") (pinfunction "P1_4") (pintype "passive"))
    )
    (net (code "102") (name "unconnected-(S8-S1-Pad2)") (class "Default")
      (node (ref "S8") (pin "2") (pinfunction "S1_2") (pintype "passive"))
    )
    (net (code "103") (name "unconnected-(S9-P1-Pad4)") (class "Default")
      (node (ref "S9") (pin "4") (pinfunction "P1_4") (pintype "passive"))
    )
    (net (code "104") (name "unconnected-(S9-S-Pad1)") (class "Default")
      (node (ref "S9") (pin "1") (pinfunction "S_1") (pintype "passive"))
    )
    (net (code "105") (name "unconnected-(S10-P1-Pad4)") (class "Default")
      (node (ref "S10") (pin "4") (pinfunction "P1_4") (pintype "passive"))
    )
    (net (code "106") (name "unconnected-(S10-S-Pad1)") (class "Default")
      (node (ref "S10") (pin "1") (pinfunction "S_1") (pintype "passive"))
    )
    (net (code "107") (name "unconnected-(U1-PIO2_6{slash}CT32B0_MAT1-Pad1)") (class "Default")
      (node (ref "U1") (pin "1") (pinfunction "PIO2_6/CT32B0_MAT1_1") (pintype "bidirectional"))
    )
    (net (code "108") (name "unconnected-(U1-PIO2_7{slash}CT32B0_MAT2{slash}RXD-Pad11)") (class "Default")
      (node (ref "U1") (pin "11") (pinfunction "PIO2_7/CT32B0_MAT2/RXD_11") (pintype "bidirectional"))
    )
    (net (code "109") (name "unconnected-(U1-PIO3_3{slash}RI{slash}CT16B0_CAP0-Pad48)") (class "Default")
      (node (ref "U1") (pin "48") (pinfunction "PIO3_3/RI/CT16B0_CAP0_48") (pintype "bidirectional"))
    )
  )
)
